# esp32_ssd1306.net
KiCad netlist of a schematic drawn in EAGLE
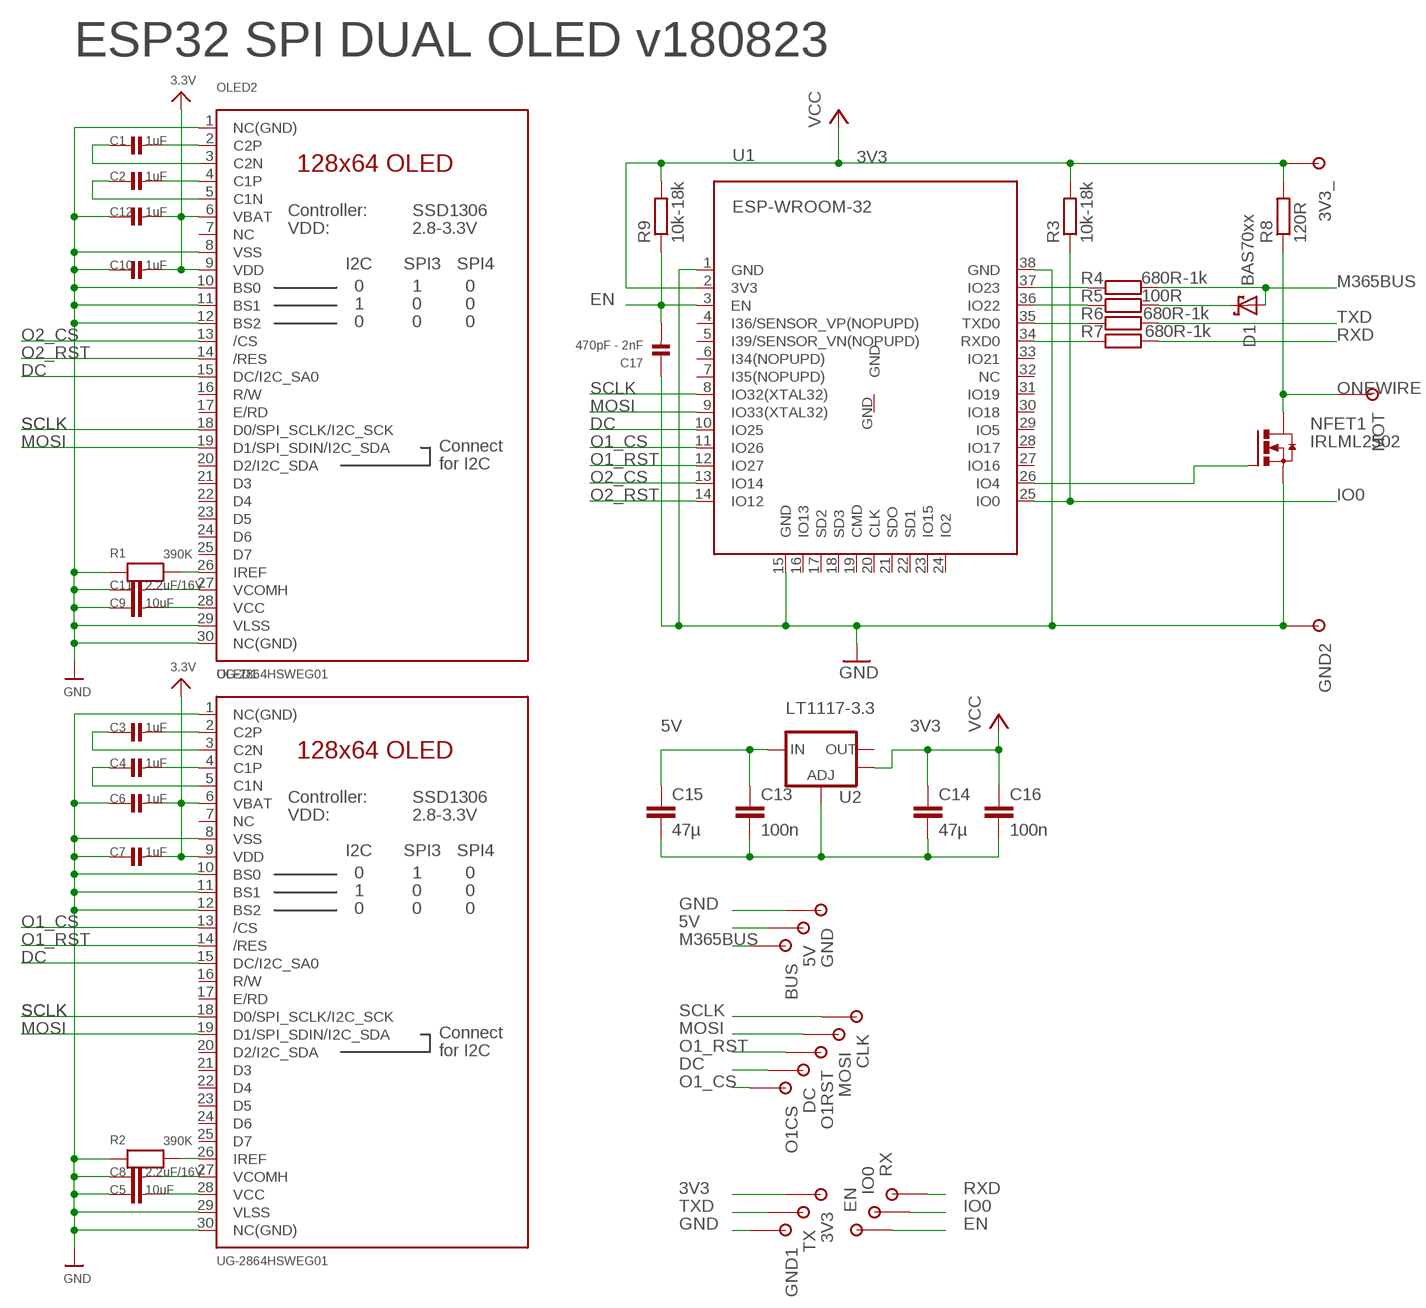
[diagram p0: schematic, sheet 1]

(export (version "E")
  (design (tool "Eeschema 10.0.6"))
  (components
    (comp (ref "3V3")
      (value "PAD1")
      (footprint "eagle-import:PAD1")
      (libsource (lib "eagle-import") (part "PAD1"))
    )
    (comp (ref "3V3_")
      (value "PAD1")
      (footprint "eagle-import:PAD1")
      (libsource (lib "eagle-import") (part "PAD1"))
    )
    (comp (ref "5V")
      (value "PAD1")
      (footprint "eagle-import:PAD1")
      (libsource (lib "eagle-import") (part "PAD1"))
    )
    (comp (ref "BUS")
      (value "PAD1")
      (footprint "eagle-import:PAD1")
      (libsource (lib "eagle-import") (part "PAD1"))
    )
    (comp (ref "C1")
      (value "1uF")
      (footprint "eagle-import:0805")
      (libsource (lib "eagle-import") (part "CAP_CERAMIC0805"))
    )
    (comp (ref "C2")
      (value "1uF")
      (footprint "eagle-import:0805")
      (libsource (lib "eagle-import") (part "CAP_CERAMIC0805"))
    )
    (comp (ref "C3")
      (value "1uF")
      (footprint "eagle-import:0805")
      (libsource (lib "eagle-import") (part "CAP_CERAMIC0805"))
    )
    (comp (ref "C4")
      (value "1uF")
      (footprint "eagle-import:0805")
      (libsource (lib "eagle-import") (part "CAP_CERAMIC0805"))
    )
    (comp (ref "C5")
      (value "10uF")
      (footprint "eagle-import:0805")
      (libsource (lib "eagle-import") (part "CAP_CERAMIC0805"))
    )
    (comp (ref "C6")
      (value "1uF")
      (footprint "eagle-import:0805")
      (libsource (lib "eagle-import") (part "CAP_CERAMIC0805"))
    )
    (comp (ref "C7")
      (value "1uF")
      (footprint "eagle-import:0805")
      (libsource (lib "eagle-import") (part "CAP_CERAMIC0805"))
    )
    (comp (ref "C8")
      (value "2.2uF/16V")
      (footprint "eagle-import:0805")
      (libsource (lib "eagle-import") (part "CAP_CERAMIC0805"))
    )
    (comp (ref "C9")
      (value "10uF")
      (footprint "eagle-import:0805")
      (libsource (lib "eagle-import") (part "CAP_CERAMIC0805"))
    )
    (comp (ref "C10")
      (value "1uF")
      (footprint "eagle-import:0805")
      (libsource (lib "eagle-import") (part "CAP_CERAMIC0805"))
    )
    (comp (ref "C11")
      (value "2.2uF/16V")
      (footprint "eagle-import:0805")
      (libsource (lib "eagle-import") (part "CAP_CERAMIC0805"))
    )
    (comp (ref "C12")
      (value "1uF")
      (footprint "eagle-import:0805")
      (libsource (lib "eagle-import") (part "CAP_CERAMIC0805"))
    )
    (comp (ref "C13")
      (value "100n")
      (footprint "eagle-import:C0805K")
      (libsource (lib "eagle-import") (part "C-EUC0805K"))
    )
    (comp (ref "C14")
      (value "47µ")
      (footprint "eagle-import:C1210K")
      (libsource (lib "eagle-import") (part "C-EUC1210K"))
    )
    (comp (ref "C15")
      (value "47µ")
      (footprint "eagle-import:C1210K")
      (libsource (lib "eagle-import") (part "C-EUC1210K"))
    )
    (comp (ref "C16")
      (value "100n")
      (footprint "eagle-import:C0805K")
      (libsource (lib "eagle-import") (part "C-EUC0805K"))
    )
    (comp (ref "C17")
      (value "470pF - 2nF")
      (footprint "eagle-import:0805")
      (libsource (lib "eagle-import") (part "CAP_CERAMIC0805"))
    )
    (comp (ref "CLK")
      (value "PAD1")
      (footprint "eagle-import:PAD1")
      (libsource (lib "eagle-import") (part "PAD1"))
    )
    (comp (ref "D1")
      (value "BAS70xx")
      (footprint "eagle-import:SOT23")
      (libsource (lib "eagle-import") (part "BAS70"))
    )
    (comp (ref "DC")
      (value "PAD1")
      (footprint "eagle-import:PAD1")
      (libsource (lib "eagle-import") (part "PAD1"))
    )
    (comp (ref "EN")
      (value "PAD1")
      (footprint "eagle-import:PAD1")
      (libsource (lib "eagle-import") (part "PAD1"))
    )
    (comp (ref "GND")
      (value "PAD1")
      (footprint "eagle-import:PAD1")
      (libsource (lib "eagle-import") (part "PAD1"))
    )
    (comp (ref "GND1")
      (value "PAD1")
      (footprint "eagle-import:PAD1")
      (libsource (lib "eagle-import") (part "PAD1"))
    )
    (comp (ref "GND2")
      (value "PAD1")
      (footprint "eagle-import:PAD1")
      (libsource (lib "eagle-import") (part "PAD1"))
    )
    (comp (ref "IO0")
      (value "PAD1")
      (footprint "eagle-import:PAD1")
      (libsource (lib "eagle-import") (part "PAD1"))
    )
    (comp (ref "MOSI")
      (value "PAD1")
      (footprint "eagle-import:PAD1")
      (libsource (lib "eagle-import") (part "PAD1"))
    )
    (comp (ref "MOT")
      (value "PAD1")
      (footprint "eagle-import:PAD1")
      (libsource (lib "eagle-import") (part "PAD1"))
    )
    (comp (ref "NFET1")
      (value "IRLML2502")
      (footprint "eagle-import:MICRO3")
      (libsource (lib "eagle-import") (part "IRLML2502"))
    )
    (comp (ref "O1CS")
      (value "PAD1")
      (footprint "eagle-import:PAD1")
      (libsource (lib "eagle-import") (part "PAD1"))
    )
    (comp (ref "O1RST")
      (value "PAD1")
      (footprint "eagle-import:PAD1")
      (libsource (lib "eagle-import") (part "PAD1"))
    )
    (comp (ref "OLED1")
      (value "UG-2864HSWEG01")
      (footprint "eagle-import:UG-2864HSWEG01_0.96IN_WRAPAROUND")
      (libsource (lib "eagle-import") (part "DISP_OLED_UG-2864HSWEG010.96{dblquote}"))
    )
    (comp (ref "OLED2")
      (value "UG-2864HSWEG01")
      (footprint "eagle-import:UG-2864HSWEG01_0.96IN_WRAPAROUND")
      (libsource (lib "eagle-import") (part "DISP_OLED_UG-2864HSWEG010.96{dblquote}"))
    )
    (comp (ref "R1")
      (value "390K")
      (footprint "eagle-import:0805")
      (libsource (lib "eagle-import") (part "RESISTOR0805"))
    )
    (comp (ref "R2")
      (value "390K")
      (footprint "eagle-import:0805")
      (libsource (lib "eagle-import") (part "RESISTOR0805"))
    )
    (comp (ref "R3")
      (value "10k-18k")
      (footprint "eagle-import:R0805")
      (libsource (lib "eagle-import") (part "R-EU_R0805"))
    )
    (comp (ref "R4")
      (value "680R-1k")
      (footprint "eagle-import:R0805")
      (libsource (lib "eagle-import") (part "R-EU_R0805"))
    )
    (comp (ref "R5")
      (value "100R")
      (footprint "eagle-import:R0805")
      (libsource (lib "eagle-import") (part "R-EU_R0805"))
    )
    (comp (ref "R6")
      (value "680R-1k")
      (footprint "eagle-import:R0805")
      (libsource (lib "eagle-import") (part "R-EU_R0805"))
    )
    (comp (ref "R7")
      (value "680R-1k")
      (footprint "eagle-import:R0805")
      (libsource (lib "eagle-import") (part "R-EU_R0805"))
    )
    (comp (ref "R8")
      (value "120R")
      (footprint "eagle-import:R0805")
      (libsource (lib "eagle-import") (part "R-EU_R0805"))
    )
    (comp (ref "R9")
      (value "10k-18k")
      (footprint "eagle-import:R0805")
      (libsource (lib "eagle-import") (part "R-EU_R0805"))
    )
    (comp (ref "RX")
      (value "PAD1")
      (footprint "eagle-import:PAD1")
      (libsource (lib "eagle-import") (part "PAD1"))
    )
    (comp (ref "TX")
      (value "PAD1")
      (footprint "eagle-import:PAD1")
      (libsource (lib "eagle-import") (part "PAD1"))
    )
    (comp (ref "U1")
      (value "ESP-WROOM-32")
      (footprint "eagle-import:ESP-WROOM-32")
      (libsource (lib "eagle-import") (part "ESP-WROOM-32"))
    )
    (comp (ref "U2")
      (value "LT1117-3.3")
      (footprint "eagle-import:SOT223")
      (libsource (lib "eagle-import") (part "V_REG_LM1117SOT223"))
    )
  )
  (nets
    (net (code "1") (name "/5V") (class "Default")
      (node (ref "5V") (pin "P$1") (pinfunction "PIN1_P$1") (pintype "bidirectional"))
      (node (ref "C13") (pin "1") (pinfunction "1_1") (pintype "passive"))
      (node (ref "C15") (pin "1") (pinfunction "1_1") (pintype "passive"))
      (node (ref "U2") (pin "3") (pinfunction "IN_3") (pintype "input"))
    )
    (net (code "2") (name "/DC") (class "Default")
      (node (ref "DC") (pin "P$1") (pinfunction "PIN1_P$1") (pintype "bidirectional"))
      (node (ref "OLED1") (pin "15") (pinfunction "DC/I2C_SA0_15") (pintype "input"))
      (node (ref "OLED2") (pin "15") (pinfunction "DC/I2C_SA0_15") (pintype "input"))
      (node (ref "U1") (pin "10") (pinfunction "IO25_10") (pintype "bidirectional"))
    )
    (net (code "3") (name "/EN") (class "Default")
      (node (ref "C17") (pin "2") (pinfunction "P$2_2") (pintype "passive"))
      (node (ref "EN") (pin "P$1") (pinfunction "PIN1_P$1") (pintype "bidirectional"))
      (node (ref "R9") (pin "1") (pinfunction "1_1") (pintype "passive"))
      (node (ref "U1") (pin "3") (pinfunction "EN_3") (pintype "bidirectional"))
    )
    (net (code "4") (name "/IO0") (class "Default")
      (node (ref "IO0") (pin "P$1") (pinfunction "PIN1_P$1") (pintype "bidirectional"))
      (node (ref "R3") (pin "1") (pinfunction "1_1") (pintype "passive"))
      (node (ref "U1") (pin "25") (pinfunction "IO0_25") (pintype "bidirectional"))
    )
    (net (code "5") (name "/M365BUS") (class "Default")
      (node (ref "BUS") (pin "P$1") (pinfunction "PIN1_P$1") (pintype "bidirectional"))
      (node (ref "D1") (pin "1") (pinfunction "A_1") (pintype "passive"))
      (node (ref "R4") (pin "2") (pinfunction "2_2") (pintype "passive"))
    )
    (net (code "6") (name "/MOSI") (class "Default")
      (node (ref "MOSI") (pin "P$1") (pinfunction "PIN1_P$1") (pintype "bidirectional"))
      (node (ref "OLED1") (pin "19") (pinfunction "D1/SPI_SDIN/I2C_SDA_19") (pintype "bidirectional"))
      (node (ref "OLED2") (pin "19") (pinfunction "D1/SPI_SDIN/I2C_SDA_19") (pintype "bidirectional"))
      (node (ref "U1") (pin "9") (pinfunction "IO33(XTAL32)_9") (pintype "bidirectional"))
    )
    (net (code "7") (name "/O1_CS") (class "Default")
      (node (ref "O1CS") (pin "P$1") (pinfunction "PIN1_P$1") (pintype "bidirectional"))
      (node (ref "OLED1") (pin "13") (pinfunction "/CS_13") (pintype "input"))
      (node (ref "U1") (pin "11") (pinfunction "IO26_11") (pintype "bidirectional"))
    )
    (net (code "8") (name "/O1_RST") (class "Default")
      (node (ref "O1RST") (pin "P$1") (pinfunction "PIN1_P$1") (pintype "bidirectional"))
      (node (ref "OLED1") (pin "14") (pinfunction "/RES_14") (pintype "input"))
      (node (ref "U1") (pin "12") (pinfunction "IO27_12") (pintype "bidirectional"))
    )
    (net (code "9") (name "/O2_CS") (class "Default")
      (node (ref "OLED2") (pin "13") (pinfunction "/CS_13") (pintype "input"))
      (node (ref "U1") (pin "13") (pinfunction "IO14_13") (pintype "bidirectional"))
    )
    (net (code "10") (name "/O2_RST") (class "Default")
      (node (ref "OLED2") (pin "14") (pinfunction "/RES_14") (pintype "input"))
      (node (ref "U1") (pin "14") (pinfunction "IO12_14") (pintype "bidirectional"))
    )
    (net (code "11") (name "/ONEWIRE") (class "Default")
      (node (ref "MOT") (pin "P$1") (pinfunction "PIN1_P$1") (pintype "bidirectional"))
      (node (ref "NFET1") (pin "3") (pinfunction "D_3") (pintype "passive"))
      (node (ref "R8") (pin "1") (pinfunction "1_1") (pintype "passive"))
    )
    (net (code "12") (name "/RXD") (class "Default")
      (node (ref "R7") (pin "2") (pinfunction "2_2") (pintype "passive"))
      (node (ref "RX") (pin "P$1") (pinfunction "PIN1_P$1") (pintype "bidirectional"))
    )
    (net (code "13") (name "/SCLK") (class "Default")
      (node (ref "CLK") (pin "P$1") (pinfunction "PIN1_P$1") (pintype "bidirectional"))
      (node (ref "OLED1") (pin "18") (pinfunction "D0/SPI_SCLK/I2C_SCK_18") (pintype "bidirectional"))
      (node (ref "OLED2") (pin "18") (pinfunction "D0/SPI_SCLK/I2C_SCK_18") (pintype "bidirectional"))
      (node (ref "U1") (pin "8") (pinfunction "IO32(XTAL32)_8") (pintype "bidirectional"))
    )
    (net (code "14") (name "/TXD") (class "Default")
      (node (ref "R6") (pin "2") (pinfunction "2_2") (pintype "passive"))
      (node (ref "TX") (pin "P$1") (pinfunction "PIN1_P$1") (pintype "bidirectional"))
    )
    (net (code "15") (name "3.3V") (class "Default")
      (node (ref "3V3") (pin "P$1") (pinfunction "PIN1_P$1") (pintype "bidirectional"))
      (node (ref "3V3_") (pin "P$1") (pinfunction "PIN1_P$1") (pintype "bidirectional"))
      (node (ref "C10") (pin "2") (pinfunction "P$2_2") (pintype "passive"))
      (node (ref "C12") (pin "2") (pinfunction "P$2_2") (pintype "passive"))
      (node (ref "C14") (pin "1") (pinfunction "1_1") (pintype "passive"))
      (node (ref "C16") (pin "1") (pinfunction "1_1") (pintype "passive"))
      (node (ref "C6") (pin "2") (pinfunction "P$2_2") (pintype "passive"))
      (node (ref "C7") (pin "2") (pinfunction "P$2_2") (pintype "passive"))
      (node (ref "OLED1") (pin "6") (pinfunction "VBAT_6") (pintype "input"))
      (node (ref "OLED1") (pin "9") (pinfunction "VDD_9") (pintype "power_in"))
      (node (ref "OLED2") (pin "6") (pinfunction "VBAT_6") (pintype "input"))
      (node (ref "OLED2") (pin "9") (pinfunction "VDD_9") (pintype "power_in"))
      (node (ref "R3") (pin "2") (pinfunction "2_2") (pintype "passive"))
      (node (ref "R8") (pin "2") (pinfunction "2_2") (pintype "passive"))
      (node (ref "R9") (pin "2") (pinfunction "2_2") (pintype "passive"))
      (node (ref "U1") (pin "2") (pinfunction "3V3_2") (pintype "bidirectional"))
      (node (ref "U2") (pin "4") (pinfunction "OUT_4") (pintype "output"))
    )
    (net (code "16") (name "GND") (class "Default")
      (node (ref "C10") (pin "1") (pinfunction "P$1_1") (pintype "passive"))
      (node (ref "C11") (pin "1") (pinfunction "P$1_1") (pintype "passive"))
      (node (ref "C12") (pin "1") (pinfunction "P$1_1") (pintype "passive"))
      (node (ref "C13") (pin "2") (pinfunction "2_2") (pintype "passive"))
      (node (ref "C14") (pin "2") (pinfunction "2_2") (pintype "passive"))
      (node (ref "C15") (pin "2") (pinfunction "2_2") (pintype "passive"))
      (node (ref "C16") (pin "2") (pinfunction "2_2") (pintype "passive"))
      (node (ref "C17") (pin "1") (pinfunction "P$1_1") (pintype "passive"))
      (node (ref "C5") (pin "1") (pinfunction "P$1_1") (pintype "passive"))
      (node (ref "C6") (pin "1") (pinfunction "P$1_1") (pintype "passive"))
      (node (ref "C7") (pin "1") (pinfunction "P$1_1") (pintype "passive"))
      (node (ref "C8") (pin "1") (pinfunction "P$1_1") (pintype "passive"))
      (node (ref "C9") (pin "1") (pinfunction "P$1_1") (pintype "passive"))
      (node (ref "GND") (pin "P$1") (pinfunction "PIN1_P$1") (pintype "bidirectional"))
      (node (ref "GND1") (pin "P$1") (pinfunction "PIN1_P$1") (pintype "bidirectional"))
      (node (ref "GND2") (pin "P$1") (pinfunction "PIN1_P$1") (pintype "bidirectional"))
      (node (ref "NFET1") (pin "2") (pinfunction "S_2") (pintype "passive"))
      (node (ref "OLED1") (pin "1") (pinfunction "NC(GND)_1") (pintype "input"))
      (node (ref "OLED1") (pin "10") (pinfunction "BS0_10") (pintype "input"))
      (node (ref "OLED1") (pin "11") (pinfunction "BS1_11") (pintype "input"))
      (node (ref "OLED1") (pin "12") (pinfunction "BS2_12") (pintype "input"))
      (node (ref "OLED1") (pin "29") (pinfunction "VLSS_29") (pintype "power_in"))
      (node (ref "OLED1") (pin "30") (pinfunction "NC(GND)_30") (pintype "input"))
      (node (ref "OLED1") (pin "8") (pinfunction "VSS_8") (pintype "power_in"))
      (node (ref "OLED2") (pin "1") (pinfunction "NC(GND)_1") (pintype "input"))
      (node (ref "OLED2") (pin "10") (pinfunction "BS0_10") (pintype "input"))
      (node (ref "OLED2") (pin "11") (pinfunction "BS1_11") (pintype "input"))
      (node (ref "OLED2") (pin "12") (pinfunction "BS2_12") (pintype "input"))
      (node (ref "OLED2") (pin "29") (pinfunction "VLSS_29") (pintype "power_in"))
      (node (ref "OLED2") (pin "30") (pinfunction "NC(GND)_30") (pintype "input"))
      (node (ref "OLED2") (pin "8") (pinfunction "VSS_8") (pintype "power_in"))
      (node (ref "R1") (pin "1") (pinfunction "1_1") (pintype "passive"))
      (node (ref "R2") (pin "1") (pinfunction "1_1") (pintype "passive"))
      (node (ref "U1") (pin "1") (pinfunction "GND_1") (pintype "bidirectional"))
      (node (ref "U1") (pin "15") (pinfunction "GND_15") (pintype "bidirectional"))
      (node (ref "U1") (pin "38") (pinfunction "GND_38") (pintype "bidirectional"))
      (node (ref "U2") (pin "1") (pinfunction "ADJ_1") (pintype "input"))
    )
    (net (code "17") (name "Net-(C1-P$1)") (class "Default")
      (node (ref "C1") (pin "1") (pinfunction "P$1_1") (pintype "passive"))
      (node (ref "OLED2") (pin "3") (pinfunction "C2N_3") (pintype "input"))
    )
    (net (code "18") (name "Net-(C1-P$2)") (class "Default")
      (node (ref "C1") (pin "2") (pinfunction "P$2_2") (pintype "passive"))
      (node (ref "OLED2") (pin "2") (pinfunction "C2P_2") (pintype "input"))
    )
    (net (code "19") (name "Net-(C2-P$1)") (class "Default")
      (node (ref "C2") (pin "1") (pinfunction "P$1_1") (pintype "passive"))
      (node (ref "OLED2") (pin "5") (pinfunction "C1N_5") (pintype "input"))
    )
    (net (code "20") (name "Net-(C2-P$2)") (class "Default")
      (node (ref "C2") (pin "2") (pinfunction "P$2_2") (pintype "passive"))
      (node (ref "OLED2") (pin "4") (pinfunction "C1P_4") (pintype "input"))
    )
    (net (code "21") (name "Net-(C3-P$1)") (class "Default")
      (node (ref "C3") (pin "1") (pinfunction "P$1_1") (pintype "passive"))
      (node (ref "OLED1") (pin "3") (pinfunction "C2N_3") (pintype "input"))
    )
    (net (code "22") (name "Net-(C3-P$2)") (class "Default")
      (node (ref "C3") (pin "2") (pinfunction "P$2_2") (pintype "passive"))
      (node (ref "OLED1") (pin "2") (pinfunction "C2P_2") (pintype "input"))
    )
    (net (code "23") (name "Net-(C4-P$1)") (class "Default")
      (node (ref "C4") (pin "1") (pinfunction "P$1_1") (pintype "passive"))
      (node (ref "OLED1") (pin "5") (pinfunction "C1N_5") (pintype "input"))
    )
    (net (code "24") (name "Net-(C4-P$2)") (class "Default")
      (node (ref "C4") (pin "2") (pinfunction "P$2_2") (pintype "passive"))
      (node (ref "OLED1") (pin "4") (pinfunction "C1P_4") (pintype "input"))
    )
    (net (code "25") (name "Net-(C5-P$2)") (class "Default")
      (node (ref "C5") (pin "2") (pinfunction "P$2_2") (pintype "passive"))
      (node (ref "OLED1") (pin "28") (pinfunction "VCC_28") (pintype "power_in"))
    )
    (net (code "26") (name "Net-(C8-P$2)") (class "Default")
      (node (ref "C8") (pin "2") (pinfunction "P$2_2") (pintype "passive"))
      (node (ref "OLED1") (pin "27") (pinfunction "VCOMH_27") (pintype "output"))
    )
    (net (code "27") (name "Net-(C9-P$2)") (class "Default")
      (node (ref "C9") (pin "2") (pinfunction "P$2_2") (pintype "passive"))
      (node (ref "OLED2") (pin "28") (pinfunction "VCC_28") (pintype "power_in"))
    )
    (net (code "28") (name "Net-(C11-P$2)") (class "Default")
      (node (ref "C11") (pin "2") (pinfunction "P$2_2") (pintype "passive"))
      (node (ref "OLED2") (pin "27") (pinfunction "VCOMH_27") (pintype "output"))
    )
    (net (code "29") (name "Net-(D1-C)") (class "Default")
      (node (ref "D1") (pin "3") (pinfunction "C_3") (pintype "passive"))
      (node (ref "R5") (pin "2") (pinfunction "2_2") (pintype "passive"))
    )
    (net (code "30") (name "Net-(NFET1-G)") (class "Default")
      (node (ref "NFET1") (pin "1") (pinfunction "G_1") (pintype "passive"))
      (node (ref "U1") (pin "26") (pinfunction "IO4_26") (pintype "bidirectional"))
    )
    (net (code "31") (name "Net-(OLED1-IREF)") (class "Default")
      (node (ref "OLED1") (pin "26") (pinfunction "IREF_26") (pintype "input"))
      (node (ref "R2") (pin "2") (pinfunction "2_2") (pintype "passive"))
    )
    (net (code "32") (name "Net-(OLED2-IREF)") (class "Default")
      (node (ref "OLED2") (pin "26") (pinfunction "IREF_26") (pintype "input"))
      (node (ref "R1") (pin "2") (pinfunction "2_2") (pintype "passive"))
    )
    (net (code "33") (name "Net-(U1-IO22)") (class "Default")
      (node (ref "R5") (pin "1") (pinfunction "1_1") (pintype "passive"))
      (node (ref "U1") (pin "36") (pinfunction "IO22_36") (pintype "bidirectional"))
    )
    (net (code "34") (name "Net-(U1-IO23)") (class "Default")
      (node (ref "R4") (pin "1") (pinfunction "1_1") (pintype "passive"))
      (node (ref "U1") (pin "37") (pinfunction "IO23_37") (pintype "bidirectional"))
    )
    (net (code "35") (name "Net-(U1-RXD0)") (class "Default")
      (node (ref "R7") (pin "1") (pinfunction "1_1") (pintype "passive"))
      (node (ref "U1") (pin "34") (pinfunction "RXD0_34") (pintype "bidirectional"))
    )
    (net (code "36") (name "Net-(U1-TXD0)") (class "Default")
      (node (ref "R6") (pin "1") (pinfunction "1_1") (pintype "passive"))
      (node (ref "U1") (pin "35") (pinfunction "TXD0_35") (pintype "bidirectional"))
    )
    (net (code "37") (name "unconnected-(OLED1-D2{slash}I2C_SDA-Pad20)") (class "Default")
      (node (ref "OLED1") (pin "20") (pinfunction "D2/I2C_SDA_20") (pintype "bidirectional"))
    )
    (net (code "38") (name "unconnected-(OLED1-D3-Pad21)") (class "Default")
      (node (ref "OLED1") (pin "21") (pinfunction "D3_21") (pintype "bidirectional"))
    )
    (net (code "39") (name "unconnected-(OLED1-D4-Pad22)") (class "Default")
      (node (ref "OLED1") (pin "22") (pinfunction "D4_22") (pintype "bidirectional"))
    )
    (net (code "40") (name "unconnected-(OLED1-D5-Pad23)") (class "Default")
      (node (ref "OLED1") (pin "23") (pinfunction "D5_23") (pintype "bidirectional"))
    )
    (net (code "41") (name "unconnected-(OLED1-D6-Pad24)") (class "Default")
      (node (ref "OLED1") (pin "24") (pinfunction "D6_24") (pintype "bidirectional"))
    )
    (net (code "42") (name "unconnected-(OLED1-D7-Pad25)") (class "Default")
      (node (ref "OLED1") (pin "25") (pinfunction "D7_25") (pintype "bidirectional"))
    )
    (net (code "43") (name "unconnected-(OLED1-E{slash}RD-Pad17)") (class "Default")
      (node (ref "OLED1") (pin "17") (pinfunction "E/RD_17") (pintype "input"))
    )
    (net (code "44") (name "unconnected-(OLED1-NC-Pad7)") (class "Default")
      (node (ref "OLED1") (pin "7") (pinfunction "NC_7") (pintype "no_connect"))
    )
    (net (code "45") (name "unconnected-(OLED1-R{slash}W-Pad16)") (class "Default")
      (node (ref "OLED1") (pin "16") (pinfunction "R/W_16") (pintype "input"))
    )
    (net (code "46") (name "unconnected-(OLED2-D2{slash}I2C_SDA-Pad20)") (class "Default")
      (node (ref "OLED2") (pin "20") (pinfunction "D2/I2C_SDA_20") (pintype "bidirectional"))
    )
    (net (code "47") (name "unconnected-(OLED2-D3-Pad21)") (class "Default")
      (node (ref "OLED2") (pin "21") (pinfunction "D3_21") (pintype "bidirectional"))
    )
    (net (code "48") (name "unconnected-(OLED2-D4-Pad22)") (class "Default")
      (node (ref "OLED2") (pin "22") (pinfunction "D4_22") (pintype "bidirectional"))
    )
    (net (code "49") (name "unconnected-(OLED2-D5-Pad23)") (class "Default")
      (node (ref "OLED2") (pin "23") (pinfunction "D5_23") (pintype "bidirectional"))
    )
    (net (code "50") (name "unconnected-(OLED2-D6-Pad24)") (class "Default")
      (node (ref "OLED2") (pin "24") (pinfunction "D6_24") (pintype "bidirectional"))
    )
    (net (code "51") (name "unconnected-(OLED2-D7-Pad25)") (class "Default")
      (node (ref "OLED2") (pin "25") (pinfunction "D7_25") (pintype "bidirectional"))
    )
    (net (code "52") (name "unconnected-(OLED2-E{slash}RD-Pad17)") (class "Default")
      (node (ref "OLED2") (pin "17") (pinfunction "E/RD_17") (pintype "input"))
    )
    (net (code "53") (name "unconnected-(OLED2-NC-Pad7)") (class "Default")
      (node (ref "OLED2") (pin "7") (pinfunction "NC_7") (pintype "no_connect"))
    )
    (net (code "54") (name "unconnected-(OLED2-R{slash}W-Pad16)") (class "Default")
      (node (ref "OLED2") (pin "16") (pinfunction "R/W_16") (pintype "input"))
    )
    (net (code "55") (name "unconnected-(U1-CLK-Pad20)") (class "Default")
      (node (ref "U1") (pin "20") (pinfunction "CLK_20") (pintype "bidirectional"))
    )
    (net (code "56") (name "unconnected-(U1-CMD-Pad19)") (class "Default")
      (node (ref "U1") (pin "19") (pinfunction "CMD_19") (pintype "bidirectional"))
    )
    (net (code "57") (name "unconnected-(U1-I34(NOPUPD)-Pad6)") (class "Default")
      (node (ref "U1") (pin "6") (pinfunction "I34(NOPUPD)_6") (pintype "bidirectional"))
    )
    (net (code "58") (name "unconnected-(U1-I35(NOPUPD)-Pad7)") (class "Default")
      (node (ref "U1") (pin "7") (pinfunction "I35(NOPUPD)_7") (pintype "bidirectional"))
    )
    (net (code "59") (name "unconnected-(U1-I36{slash}SENSOR_VP(NOPUPD)-Pad4)") (class "Default")
      (node (ref "U1") (pin "4") (pinfunction "I36/SENSOR_VP(NOPUPD)_4") (pintype "bidirectional"))
    )
    (net (code "60") (name "unconnected-(U1-I39{slash}SENSOR_VN(NOPUPD)-Pad5)") (class "Default")
      (node (ref "U1") (pin "5") (pinfunction "I39/SENSOR_VN(NOPUPD)_5") (pintype "bidirectional"))
    )
    (net (code "61") (name "unconnected-(U1-IO2-Pad24)") (class "Default")
      (node (ref "U1") (pin "24") (pinfunction "IO2_24") (pintype "bidirectional"))
    )
    (net (code "62") (name "unconnected-(U1-IO5-Pad29)") (class "Default")
      (node (ref "U1") (pin "29") (pinfunction "IO5_29") (pintype "bidirectional"))
    )
    (net (code "63") (name "unconnected-(U1-IO13-Pad16)") (class "Default")
      (node (ref "U1") (pin "16") (pinfunction "IO13_16") (pintype "bidirectional"))
    )
    (net (code "64") (name "unconnected-(U1-IO15-Pad23)") (class "Default")
      (node (ref "U1") (pin "23") (pinfunction "IO15_23") (pintype "bidirectional"))
    )
    (net (code "65") (name "unconnected-(U1-IO16-Pad27)") (class "Default")
      (node (ref "U1") (pin "27") (pinfunction "IO16_27") (pintype "bidirectional"))
    )
    (net (code "66") (name "unconnected-(U1-IO17-Pad28)") (class "Default")
      (node (ref "U1") (pin "28") (pinfunction "IO17_28") (pintype "bidirectional"))
    )
    (net (code "67") (name "unconnected-(U1-IO18-Pad30)") (class "Default")
      (node (ref "U1") (pin "30") (pinfunction "IO18_30") (pintype "bidirectional"))
    )
    (net (code "68") (name "unconnected-(U1-IO19-Pad31)") (class "Default")
      (node (ref "U1") (pin "31") (pinfunction "IO19_31") (pintype "bidirectional"))
    )
    (net (code "69") (name "unconnected-(U1-IO21-Pad33)") (class "Default")
      (node (ref "U1") (pin "33") (pinfunction "IO21_33") (pintype "bidirectional"))
    )
    (net (code "70") (name "unconnected-(U1-NC-Pad32)") (class "Default")
      (node (ref "U1") (pin "32") (pinfunction "NC_32") (pintype "bidirectional"))
    )
    (net (code "71") (name "unconnected-(U1-PadGND)") (class "Default")
      (node (ref "U1") (pin "GND") (pinfunction "GND_GND") (pintype "bidirectional"))
    )
    (net (code "72") (name "unconnected-(U1-SD1-Pad22)") (class "Default")
      (node (ref "U1") (pin "22") (pinfunction "SD1_22") (pintype "bidirectional"))
    )
    (net (code "73") (name "unconnected-(U1-SD2-Pad17)") (class "Default")
      (node (ref "U1") (pin "17") (pinfunction "SD2_17") (pintype "bidirectional"))
    )
    (net (code "74") (name "unconnected-(U1-SD3-Pad18)") (class "Default")
      (node (ref "U1") (pin "18") (pinfunction "SD3_18") (pintype "bidirectional"))
    )
    (net (code "75") (name "unconnected-(U1-SDO-Pad21)") (class "Default")
      (node (ref "U1") (pin "21") (pinfunction "SDO_21") (pintype "bidirectional"))
    )
    (net (code "76") (name "unconnected-(U2-OUT-Pad2)") (class "Default")
      (node (ref "U2") (pin "2") (pinfunction "OUT_2") (pintype "output"))
    )
  )
)
